# NET.net
KiCad netlist of a schematic drawn in Altium Designer
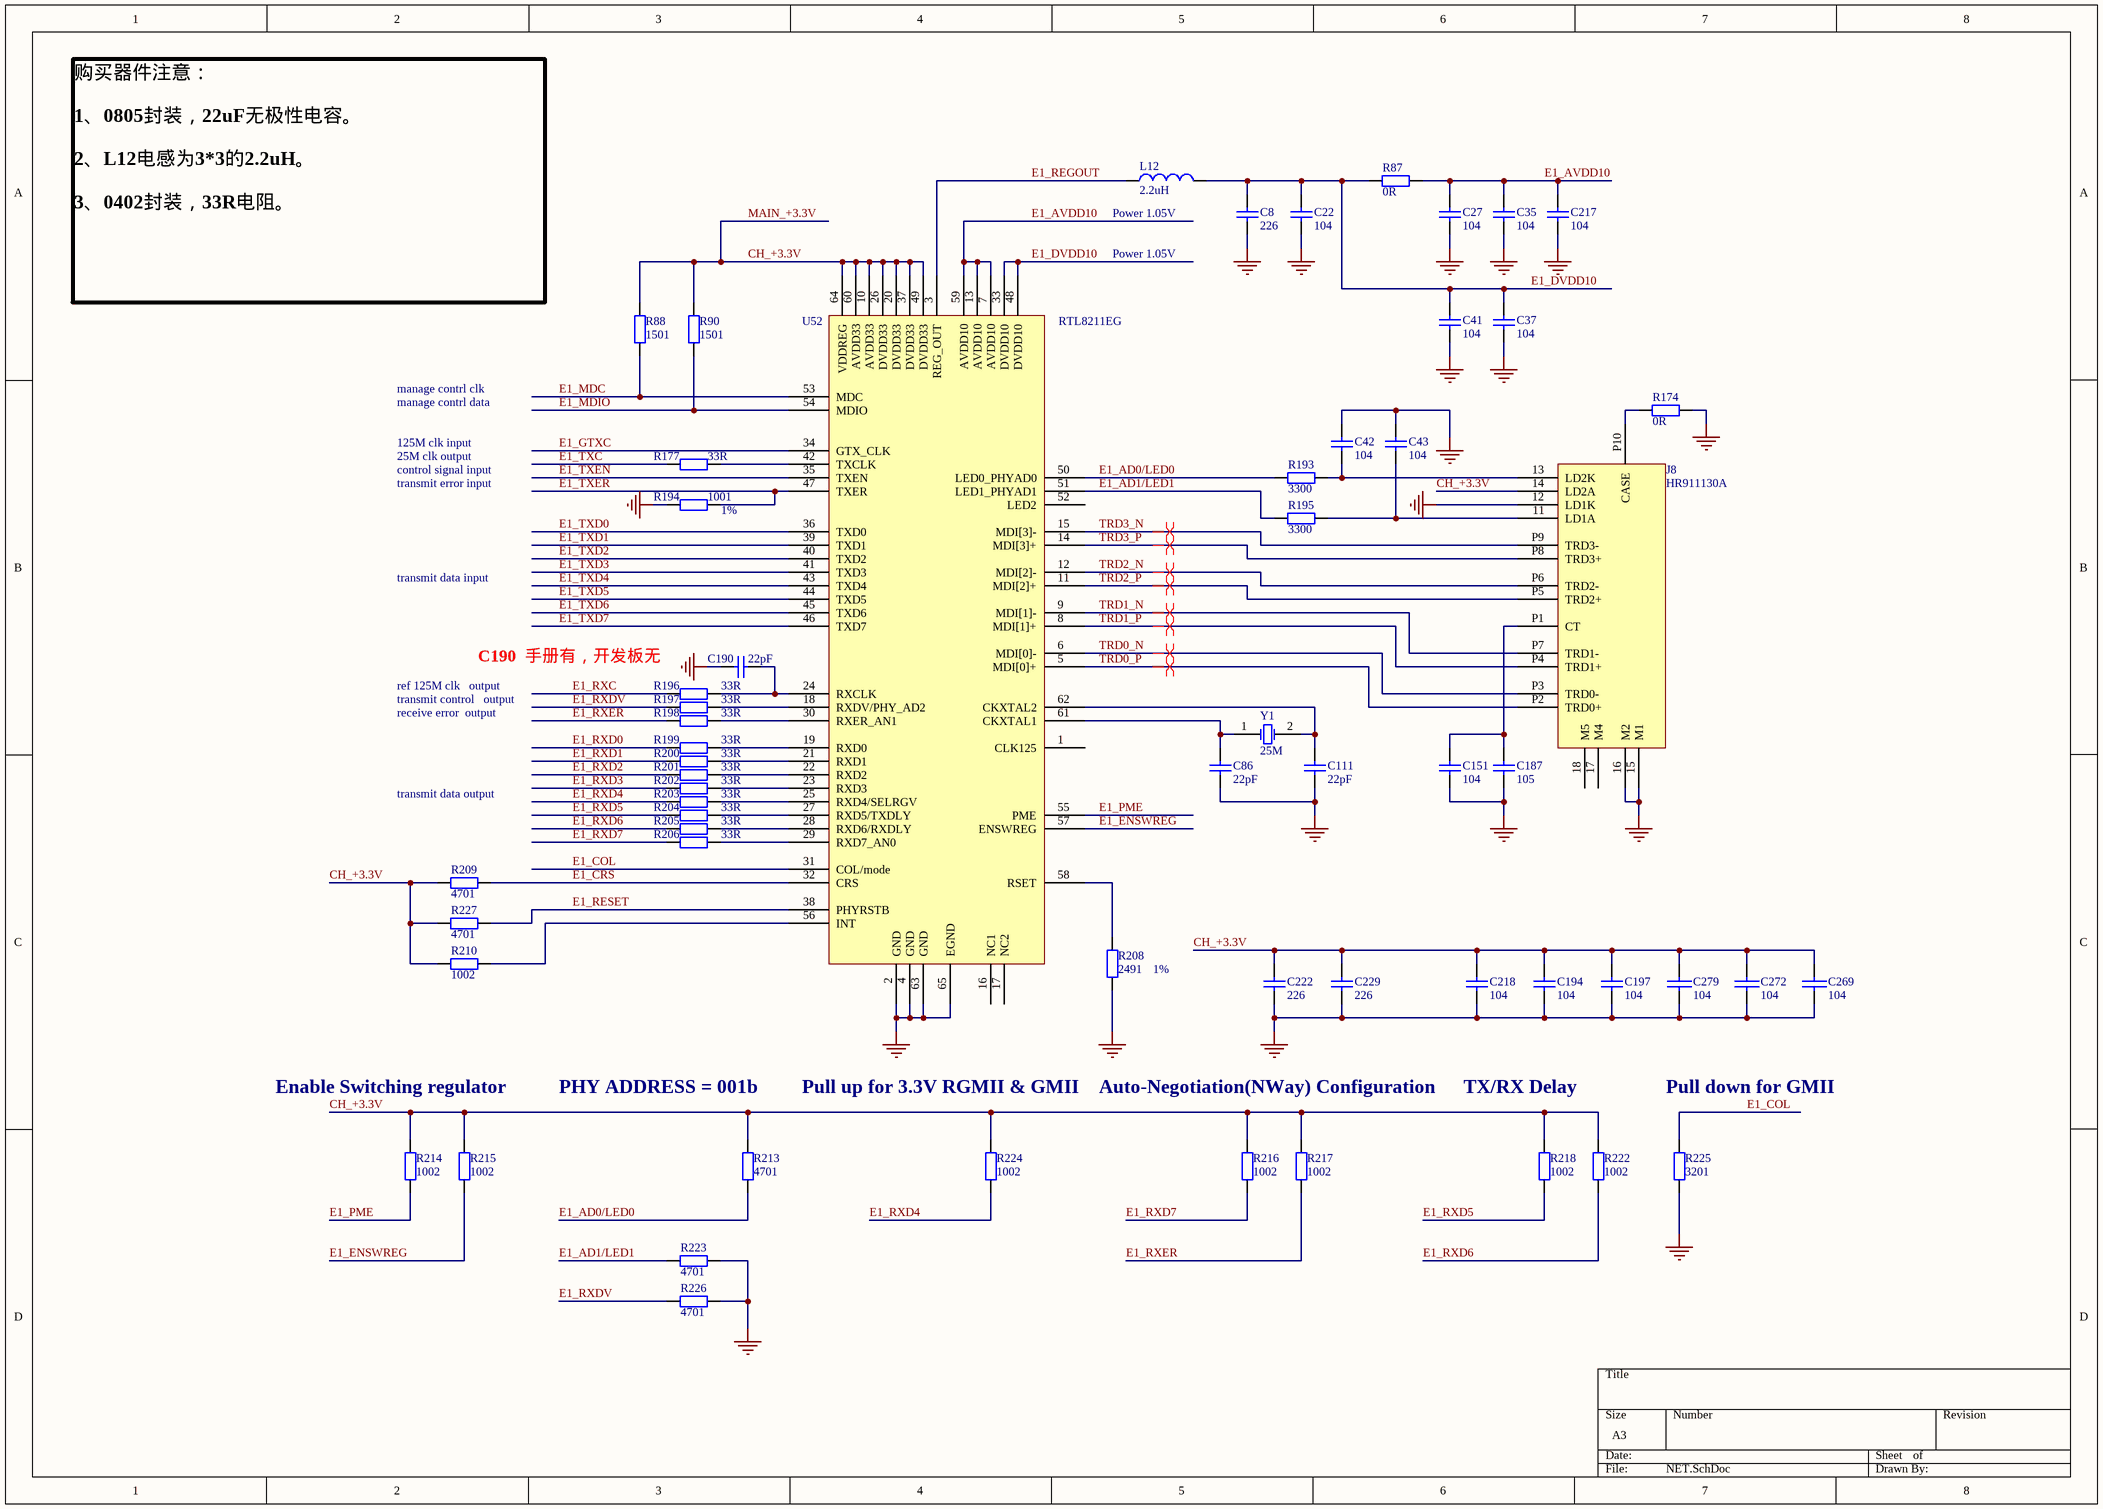
[diagram p0: NET.SchDoc]

(export (version "E")
  (design (tool "Eeschema 10.0.6"))
  (components
    (comp (ref "C8")
      (value "226")
      (footprint "0805")
      (description "Capacitor")
      (fields (field (name "PUBLISHER") "Altium Limited"))
      (libsource (lib "Miscellaneous Devices") (part "Cap"))
    )
    (comp (ref "C22")
      (value "104")
      (footprint "0402C")
      (description "Capacitor")
      (fields (field (name "PUBLISHER") "Altium Limited"))
      (libsource (lib "Miscellaneous Devices") (part "Cap"))
    )
    (comp (ref "C27")
      (value "104")
      (footprint "0402C")
      (description "Capacitor")
      (fields (field (name "PUBLISHER") "Altium Limited"))
      (libsource (lib "Miscellaneous Devices") (part "Cap"))
    )
    (comp (ref "C35")
      (value "104")
      (footprint "0402C")
      (description "Capacitor")
      (fields (field (name "PUBLISHER") "Altium Limited"))
      (libsource (lib "Miscellaneous Devices") (part "Cap"))
    )
    (comp (ref "C37")
      (value "104")
      (footprint "0402C")
      (description "Capacitor")
      (fields (field (name "PUBLISHER") "Altium Limited"))
      (libsource (lib "Miscellaneous Devices") (part "Cap"))
    )
    (comp (ref "C41")
      (value "104")
      (footprint "0402C")
      (description "Capacitor")
      (fields (field (name "PUBLISHER") "Altium Limited"))
      (libsource (lib "Miscellaneous Devices") (part "Cap"))
    )
    (comp (ref "C42")
      (value "104")
      (footprint "0402C")
      (description "Capacitor")
      (fields (field (name "PUBLISHER") "Altium Limited"))
      (libsource (lib "Miscellaneous Devices") (part "Cap"))
    )
    (comp (ref "C43")
      (value "104")
      (footprint "0402C")
      (description "Capacitor")
      (fields (field (name "PUBLISHER") "Altium Limited"))
      (libsource (lib "Miscellaneous Devices") (part "Cap"))
    )
    (comp (ref "C86")
      (value "22pF")
      (footprint "0805")
      (description "Capacitor")
      (fields (field (name "PUBLISHER") "Altium Limited"))
      (libsource (lib "Miscellaneous Devices") (part "Cap"))
    )
    (comp (ref "C111")
      (value "22pF")
      (footprint "0805")
      (description "Capacitor")
      (fields (field (name "PUBLISHER") "Altium Limited"))
      (libsource (lib "Miscellaneous Devices") (part "Cap"))
    )
    (comp (ref "C151")
      (value "104")
      (footprint "0402C")
      (description "Capacitor")
      (fields (field (name "PUBLISHER") "Altium Limited"))
      (libsource (lib "Miscellaneous Devices") (part "Cap"))
    )
    (comp (ref "C187")
      (value "105")
      (footprint "0805")
      (description "Capacitor")
      (fields (field (name "PUBLISHER") "Altium Limited"))
      (libsource (lib "Miscellaneous Devices") (part "Cap"))
    )
    (comp (ref "C190")
      (value "22pF")
      (footprint "0402")
      (description "Capacitor")
      (fields (field (name "PUBLISHER") "Altium Limited"))
      (libsource (lib "Miscellaneous Devices") (part "Cap"))
    )
    (comp (ref "C194")
      (value "104")
      (footprint "0402C")
      (description "Capacitor")
      (fields (field (name "PUBLISHER") "Altium Limited"))
      (libsource (lib "Miscellaneous Devices") (part "Cap"))
    )
    (comp (ref "C197")
      (value "104")
      (footprint "0402C")
      (description "Capacitor")
      (fields (field (name "PUBLISHER") "Altium Limited"))
      (libsource (lib "Miscellaneous Devices") (part "Cap"))
    )
    (comp (ref "C217")
      (value "104")
      (footprint "0402C")
      (description "Capacitor")
      (fields (field (name "PUBLISHER") "Altium Limited"))
      (libsource (lib "Miscellaneous Devices") (part "Cap"))
    )
    (comp (ref "C218")
      (value "104")
      (footprint "0402C")
      (description "Capacitor")
      (fields (field (name "PUBLISHER") "Altium Limited"))
      (libsource (lib "Miscellaneous Devices") (part "Cap"))
    )
    (comp (ref "C222")
      (value "226")
      (footprint "0805")
      (description "Capacitor")
      (fields (field (name "PUBLISHER") "Altium Limited"))
      (libsource (lib "Miscellaneous Devices") (part "Cap"))
    )
    (comp (ref "C229")
      (value "226")
      (footprint "0805")
      (description "Capacitor")
      (fields (field (name "PUBLISHER") "Altium Limited"))
      (libsource (lib "Miscellaneous Devices") (part "Cap"))
    )
    (comp (ref "C269")
      (value "104")
      (footprint "0402C")
      (description "Capacitor")
      (libsource (lib "*") (part "CAP"))
    )
    (comp (ref "C272")
      (value "104")
      (footprint "0402C")
      (description "Capacitor")
      (libsource (lib "*") (part "CAP"))
    )
    (comp (ref "C279")
      (value "104")
      (footprint "0402C")
      (description "Capacitor")
      (libsource (lib "*") (part "CAP"))
    )
    (comp (ref "J8") (value "HR911130A") (footprint "GE_RJ45") (libsource (lib "Schlib1") (part "HR911130A")))
    (comp (ref "L12")
      (value "2.2uH")
      (footprint "L22uH")
      (description "Inductor")
      (fields (field (name "PUBLISHER") "Altium Limited"))
      (libsource (lib "Miscellaneous Devices") (part "Inductor"))
    )
    (comp (ref "R87")
      (value "0R")
      (footprint "R0603")
      (description "Resistor")
      (fields (field (name "PUBLISHER") "Altium Limited"))
      (libsource (lib "") (part "Res2_1"))
    )
    (comp (ref "R88")
      (value "1501")
      (footprint "R0603")
      (description "Resistor")
      (fields (field (name "PUBLISHER") "Altium Limited"))
      (libsource (lib "Miscellaneous Devices") (part "Res2"))
    )
    (comp (ref "R90")
      (value "1501")
      (footprint "R0603")
      (description "Resistor")
      (fields (field (name "PUBLISHER") "Altium Limited"))
      (libsource (lib "Miscellaneous Devices") (part "Res2"))
    )
    (comp (ref "R174")
      (value "0R")
      (footprint "R0603")
      (description "Resistor")
      (fields (field (name "PUBLISHER") "Altium Limited"))
      (libsource (lib "") (part "Res2_3"))
    )
    (comp (ref "R177")
      (value "33R")
      (footprint "0402")
      (description "Resistor")
      (fields (field (name "PUBLISHER") "Altium Limited"))
      (libsource (lib "") (part "Res2_1"))
    )
    (comp (ref "R193")
      (value "3300")
      (footprint "R0603")
      (description "Resistor")
      (fields (field (name "PUBLISHER") "Altium Limited"))
      (libsource (lib "") (part "Res2_1"))
    )
    (comp (ref "R194")
      (value "1001")
      (footprint "R0603")
      (description "Resistor")
      (fields (field (name "PUBLISHER") "Altium Limited"))
      (libsource (lib "") (part "Res2_1"))
    )
    (comp (ref "R195")
      (value "3300")
      (footprint "R0603")
      (description "Resistor")
      (fields (field (name "PUBLISHER") "Altium Limited"))
      (libsource (lib "") (part "Res2_1"))
    )
    (comp (ref "R196")
      (value "33R")
      (footprint "0402")
      (description "Resistor")
      (fields (field (name "PUBLISHER") "Altium Limited"))
      (libsource (lib "") (part "Res2_1"))
    )
    (comp (ref "R197")
      (value "33R")
      (footprint "0402")
      (description "Resistor")
      (fields (field (name "PUBLISHER") "Altium Limited"))
      (libsource (lib "") (part "Res2_1"))
    )
    (comp (ref "R198")
      (value "33R")
      (footprint "0402")
      (description "Resistor")
      (fields (field (name "PUBLISHER") "Altium Limited"))
      (libsource (lib "") (part "Res2_1"))
    )
    (comp (ref "R199")
      (value "33R")
      (footprint "0402")
      (description "Resistor")
      (fields (field (name "PUBLISHER") "Altium Limited"))
      (libsource (lib "") (part "Res2_1"))
    )
    (comp (ref "R200")
      (value "33R")
      (footprint "0402")
      (description "Resistor")
      (fields (field (name "PUBLISHER") "Altium Limited"))
      (libsource (lib "") (part "Res2_1"))
    )
    (comp (ref "R201")
      (value "33R")
      (footprint "0402")
      (description "Resistor")
      (fields (field (name "PUBLISHER") "Altium Limited"))
      (libsource (lib "") (part "Res2_1"))
    )
    (comp (ref "R202")
      (value "33R")
      (footprint "0402")
      (description "Resistor")
      (fields (field (name "PUBLISHER") "Altium Limited"))
      (libsource (lib "") (part "Res2_1"))
    )
    (comp (ref "R203")
      (value "33R")
      (footprint "0402")
      (description "Resistor")
      (fields (field (name "PUBLISHER") "Altium Limited"))
      (libsource (lib "") (part "Res2_1"))
    )
    (comp (ref "R204")
      (value "33R")
      (footprint "0402")
      (description "Resistor")
      (fields (field (name "PUBLISHER") "Altium Limited"))
      (libsource (lib "") (part "Res2_3"))
    )
    (comp (ref "R205")
      (value "33R")
      (footprint "0402")
      (description "Resistor")
      (fields (field (name "PUBLISHER") "Altium Limited"))
      (libsource (lib "") (part "Res2_1"))
    )
    (comp (ref "R206")
      (value "33R")
      (footprint "0402")
      (description "Resistor")
      (fields (field (name "PUBLISHER") "Altium Limited"))
      (libsource (lib "") (part "Res2_1"))
    )
    (comp (ref "R208")
      (value "2491")
      (footprint "R0603")
      (description "Resistor")
      (fields (field (name "PUBLISHER") "Altium Limited"))
      (libsource (lib "") (part "Res2_2"))
    )
    (comp (ref "R209")
      (value "4701")
      (footprint "R0603")
      (description "Resistor")
      (fields (field (name "PUBLISHER") "Altium Limited"))
      (libsource (lib "") (part "Res2_3"))
    )
    (comp (ref "R210")
      (value "1002")
      (footprint "R0603")
      (description "Resistor")
      (fields (field (name "PUBLISHER") "Altium Limited"))
      (libsource (lib "") (part "Res2_1"))
    )
    (comp (ref "R213")
      (value "4701")
      (footprint "R0603")
      (description "Resistor")
      (fields (field (name "PUBLISHER") "Altium Limited"))
      (libsource (lib "Miscellaneous Devices") (part "Res2"))
    )
    (comp (ref "R214")
      (value "1002")
      (footprint "R0603")
      (description "Resistor")
      (fields (field (name "PUBLISHER") "Altium Limited"))
      (libsource (lib "") (part "Res2_2"))
    )
    (comp (ref "R215")
      (value "1002")
      (footprint "R0603")
      (description "Resistor")
      (fields (field (name "PUBLISHER") "Altium Limited"))
      (libsource (lib "") (part "Res2_2"))
    )
    (comp (ref "R216")
      (value "1002")
      (footprint "R0603")
      (description "Resistor")
      (fields (field (name "PUBLISHER") "Altium Limited"))
      (libsource (lib "") (part "Res2_2"))
    )
    (comp (ref "R217")
      (value "1002")
      (footprint "R0603")
      (description "Resistor")
      (fields (field (name "PUBLISHER") "Altium Limited"))
      (libsource (lib "") (part "Res2_2"))
    )
    (comp (ref "R218")
      (value "1002")
      (footprint "R0603")
      (description "Resistor")
      (fields (field (name "PUBLISHER") "Altium Limited"))
      (libsource (lib "") (part "Res2_2"))
    )
    (comp (ref "R222")
      (value "1002")
      (footprint "R0603")
      (description "Resistor")
      (fields (field (name "PUBLISHER") "Altium Limited"))
      (libsource (lib "") (part "Res2_2"))
    )
    (comp (ref "R223")
      (value "4701")
      (footprint "R0603")
      (description "Resistor")
      (fields (field (name "PUBLISHER") "Altium Limited"))
      (libsource (lib "") (part "Res2_3"))
    )
    (comp (ref "R224")
      (value "1002")
      (footprint "R0603")
      (description "Resistor")
      (fields (field (name "PUBLISHER") "Altium Limited"))
      (libsource (lib "") (part "Res2_2"))
    )
    (comp (ref "R225")
      (value "3201")
      (footprint "R0603")
      (description "Resistor")
      (fields (field (name "PUBLISHER") "Altium Limited"))
      (libsource (lib "Miscellaneous Devices") (part "Res2"))
    )
    (comp (ref "R226")
      (value "4701")
      (footprint "R0603")
      (description "Resistor")
      (fields (field (name "PUBLISHER") "Altium Limited"))
      (libsource (lib "") (part "Res2_3"))
    )
    (comp (ref "R227")
      (value "4701")
      (footprint "R0603")
      (description "Resistor")
      (fields (field (name "PUBLISHER") "Altium Limited"))
      (libsource (lib "") (part "Res2_3"))
    )
    (comp (ref "U52")
      (value "RTL8211EG")
      (footprint "QFN65-050-0909")
      (libsource (lib "Schlib1") (part "RTL8211EG"))
    )
    (comp (ref "Y1")
      (value "25M")
      (footprint "XTAL")
      (description "Crystal Oscillator")
      (fields (field (name "PUBLISHER") "Altium Limited"))
      (libsource (lib "Miscellaneous Devices") (part "XTAL"))
    )
  )
  (nets
    (net (code "1") (name "/CH_+3.3V") (class "Default")
      (node (ref "C194") (pin "2") (pinfunction "2_2") (pintype "passive"))
      (node (ref "C197") (pin "2") (pinfunction "2_2") (pintype "passive"))
      (node (ref "C218") (pin "2") (pinfunction "2_2") (pintype "passive"))
      (node (ref "C222") (pin "1") (pinfunction "1_1") (pintype "passive"))
      (node (ref "C229") (pin "1") (pinfunction "1_1") (pintype "passive"))
      (node (ref "C269") (pin "2") (pinfunction "2_2") (pintype "passive"))
      (node (ref "C272") (pin "2") (pinfunction "2_2") (pintype "passive"))
      (node (ref "C279") (pin "2") (pinfunction "2_2") (pintype "passive"))
      (node (ref "J8") (pin "14") (pinfunction "LD2A_14") (pintype "passive"))
      (node (ref "R209") (pin "1") (pinfunction "1_1") (pintype "passive"))
      (node (ref "R210") (pin "2") (pinfunction "2_2") (pintype "passive"))
      (node (ref "R213") (pin "2") (pinfunction "2_2") (pintype "passive"))
      (node (ref "R214") (pin "1") (pinfunction "1_1") (pintype "passive"))
      (node (ref "R215") (pin "1") (pinfunction "1_1") (pintype "passive"))
      (node (ref "R216") (pin "1") (pinfunction "1_1") (pintype "passive"))
      (node (ref "R217") (pin "1") (pinfunction "1_1") (pintype "passive"))
      (node (ref "R218") (pin "1") (pinfunction "1_1") (pintype "passive"))
      (node (ref "R222") (pin "1") (pinfunction "1_1") (pintype "passive"))
      (node (ref "R224") (pin "1") (pinfunction "1_1") (pintype "passive"))
      (node (ref "R227") (pin "1") (pinfunction "1_1") (pintype "passive"))
      (node (ref "R88") (pin "2") (pinfunction "2_2") (pintype "passive"))
      (node (ref "R90") (pin "2") (pinfunction "2_2") (pintype "passive"))
      (node (ref "U52") (pin "10") (pinfunction "AVDD33_10") (pintype "passive"))
      (node (ref "U52") (pin "20") (pinfunction "DVDD33_20") (pintype "passive"))
      (node (ref "U52") (pin "26") (pinfunction "DVDD33_26") (pintype "passive"))
      (node (ref "U52") (pin "37") (pinfunction "DVDD33_37") (pintype "passive"))
      (node (ref "U52") (pin "49") (pinfunction "DVDD33_49") (pintype "passive"))
      (node (ref "U52") (pin "60") (pinfunction "AVDD33_60") (pintype "passive"))
      (node (ref "U52") (pin "64") (pinfunction "VDDREG_64") (pintype "passive"))
    )
    (net (code "2") (name "/E1_AD0{slash}LED0") (class "Default")
      (node (ref "R193") (pin "2") (pinfunction "2_2") (pintype "passive"))
      (node (ref "R213") (pin "1") (pinfunction "1_1") (pintype "passive"))
      (node (ref "U52") (pin "50") (pinfunction "LED0_PHYAD0_50") (pintype "passive"))
    )
    (net (code "3") (name "/E1_AD1{slash}LED1") (class "Default")
      (node (ref "R195") (pin "2") (pinfunction "2_2") (pintype "passive"))
      (node (ref "R223") (pin "1") (pinfunction "1_1") (pintype "passive"))
      (node (ref "U52") (pin "51") (pinfunction "LED1_PHYAD1_51") (pintype "passive"))
    )
    (net (code "4") (name "/E1_AVDD10") (class "Default")
      (node (ref "C217") (pin "2") (pinfunction "2_2") (pintype "passive"))
      (node (ref "C27") (pin "2") (pinfunction "2_2") (pintype "passive"))
      (node (ref "C35") (pin "2") (pinfunction "2_2") (pintype "passive"))
      (node (ref "R87") (pin "1") (pinfunction "1_1") (pintype "passive"))
      (node (ref "U52") (pin "13") (pinfunction "AVDD10_13") (pintype "passive"))
      (node (ref "U52") (pin "59") (pinfunction "AVDD10_59") (pintype "passive"))
      (node (ref "U52") (pin "7") (pinfunction "AVDD10_7") (pintype "passive"))
    )
    (net (code "5") (name "/E1_COL") (class "Default")
      (node (ref "R225") (pin "2") (pinfunction "2_2") (pintype "passive"))
      (node (ref "U52") (pin "31") (pinfunction "COL/mode_31") (pintype "passive"))
    )
    (net (code "6") (name "/E1_CRS") (class "Default")
      (node (ref "R209") (pin "2") (pinfunction "2_2") (pintype "passive"))
      (node (ref "U52") (pin "32") (pinfunction "CRS_32") (pintype "passive"))
    )
    (net (code "7") (name "/E1_DVDD10") (class "Default")
      (node (ref "C22") (pin "2") (pinfunction "2_2") (pintype "passive"))
      (node (ref "C37") (pin "2") (pinfunction "2_2") (pintype "passive"))
      (node (ref "C41") (pin "2") (pinfunction "2_2") (pintype "passive"))
      (node (ref "C8") (pin "1") (pinfunction "1_1") (pintype "passive"))
      (node (ref "L12") (pin "2") (pinfunction "2_2") (pintype "passive"))
      (node (ref "R87") (pin "2") (pinfunction "2_2") (pintype "passive"))
      (node (ref "U52") (pin "33") (pinfunction "DVDD10_33") (pintype "passive"))
      (node (ref "U52") (pin "48") (pinfunction "DVDD10_48") (pintype "passive"))
    )
    (net (code "8") (name "/E1_ENSWREG") (class "Default")
      (node (ref "R215") (pin "2") (pinfunction "2_2") (pintype "passive"))
      (node (ref "U52") (pin "57") (pinfunction "ENSWREG_57") (pintype "passive"))
    )
    (net (code "9") (name "/E1_GTXC") (class "Default")
      (node (ref "U52") (pin "34") (pinfunction "GTX_CLK_34") (pintype "passive"))
    )
    (net (code "10") (name "/E1_MDC") (class "Default")
      (node (ref "R88") (pin "1") (pinfunction "1_1") (pintype "passive"))
      (node (ref "U52") (pin "53") (pinfunction "MDC_53") (pintype "passive"))
    )
    (net (code "11") (name "/E1_MDIO") (class "Default")
      (node (ref "R90") (pin "1") (pinfunction "1_1") (pintype "passive"))
      (node (ref "U52") (pin "54") (pinfunction "MDIO_54") (pintype "passive"))
    )
    (net (code "12") (name "/E1_PME") (class "Default")
      (node (ref "R214") (pin "2") (pinfunction "2_2") (pintype "passive"))
      (node (ref "U52") (pin "55") (pinfunction "PME_55") (pintype "passive"))
    )
    (net (code "13") (name "/E1_REGOUT") (class "Default")
      (node (ref "L12") (pin "1") (pinfunction "1_1") (pintype "passive"))
      (node (ref "U52") (pin "3") (pinfunction "REG_OUT_3") (pintype "passive"))
    )
    (net (code "14") (name "/E1_RESET") (class "Default")
      (node (ref "R227") (pin "2") (pinfunction "2_2") (pintype "passive"))
      (node (ref "U52") (pin "38") (pinfunction "PHYRSTB_38") (pintype "passive"))
    )
    (net (code "15") (name "/E1_RXC") (class "Default")
      (node (ref "R196") (pin "2") (pinfunction "2_2") (pintype "passive"))
    )
    (net (code "16") (name "/E1_RXD0") (class "Default")
      (node (ref "R199") (pin "2") (pinfunction "2_2") (pintype "passive"))
    )
    (net (code "17") (name "/E1_RXD1") (class "Default")
      (node (ref "R200") (pin "2") (pinfunction "2_2") (pintype "passive"))
    )
    (net (code "18") (name "/E1_RXD2") (class "Default")
      (node (ref "R201") (pin "2") (pinfunction "2_2") (pintype "passive"))
    )
    (net (code "19") (name "/E1_RXD3") (class "Default")
      (node (ref "R202") (pin "2") (pinfunction "2_2") (pintype "passive"))
    )
    (net (code "20") (name "/E1_RXD4") (class "Default")
      (node (ref "R203") (pin "2") (pinfunction "2_2") (pintype "passive"))
      (node (ref "R224") (pin "2") (pinfunction "2_2") (pintype "passive"))
    )
    (net (code "21") (name "/E1_RXD5") (class "Default")
      (node (ref "R204") (pin "1") (pinfunction "1_1") (pintype "passive"))
      (node (ref "R218") (pin "2") (pinfunction "2_2") (pintype "passive"))
    )
    (net (code "22") (name "/E1_RXD6") (class "Default")
      (node (ref "R205") (pin "2") (pinfunction "2_2") (pintype "passive"))
      (node (ref "R222") (pin "2") (pinfunction "2_2") (pintype "passive"))
    )
    (net (code "23") (name "/E1_RXD7") (class "Default")
      (node (ref "R206") (pin "2") (pinfunction "2_2") (pintype "passive"))
      (node (ref "R216") (pin "2") (pinfunction "2_2") (pintype "passive"))
    )
    (net (code "24") (name "/E1_RXDV") (class "Default")
      (node (ref "R197") (pin "2") (pinfunction "2_2") (pintype "passive"))
      (node (ref "R226") (pin "1") (pinfunction "1_1") (pintype "passive"))
    )
    (net (code "25") (name "/E1_RXER") (class "Default")
      (node (ref "R198") (pin "2") (pinfunction "2_2") (pintype "passive"))
      (node (ref "R217") (pin "2") (pinfunction "2_2") (pintype "passive"))
    )
    (net (code "26") (name "/E1_TXC") (class "Default")
      (node (ref "R177") (pin "2") (pinfunction "2_2") (pintype "passive"))
    )
    (net (code "27") (name "/E1_TXD0") (class "Default")
      (node (ref "U52") (pin "36") (pinfunction "TXD0_36") (pintype "passive"))
    )
    (net (code "28") (name "/E1_TXD1") (class "Default")
      (node (ref "U52") (pin "39") (pinfunction "TXD1_39") (pintype "passive"))
    )
    (net (code "29") (name "/E1_TXD2") (class "Default")
      (node (ref "U52") (pin "40") (pinfunction "TXD2_40") (pintype "passive"))
    )
    (net (code "30") (name "/E1_TXD3") (class "Default")
      (node (ref "U52") (pin "41") (pinfunction "TXD3_41") (pintype "passive"))
    )
    (net (code "31") (name "/E1_TXD4") (class "Default")
      (node (ref "U52") (pin "43") (pinfunction "TXD4_43") (pintype "passive"))
    )
    (net (code "32") (name "/E1_TXD5") (class "Default")
      (node (ref "U52") (pin "44") (pinfunction "TXD5_44") (pintype "passive"))
    )
    (net (code "33") (name "/E1_TXD6") (class "Default")
      (node (ref "U52") (pin "45") (pinfunction "TXD6_45") (pintype "passive"))
    )
    (net (code "34") (name "/E1_TXD7") (class "Default")
      (node (ref "U52") (pin "46") (pinfunction "TXD7_46") (pintype "passive"))
    )
    (net (code "35") (name "/E1_TXEN") (class "Default")
      (node (ref "U52") (pin "35") (pinfunction "TXEN_35") (pintype "passive"))
    )
    (net (code "36") (name "/E1_TXER") (class "Default")
      (node (ref "R194") (pin "1") (pinfunction "1_1") (pintype "passive"))
      (node (ref "U52") (pin "47") (pinfunction "TXER_47") (pintype "passive"))
    )
    (net (code "37") (name "/TRD0_N") (class "Default")
      (node (ref "J8") (pin "P3") (pinfunction "TRD0-_P3") (pintype "passive"))
      (node (ref "U52") (pin "6") (pinfunction "MDI[0]-_6") (pintype "passive"))
    )
    (net (code "38") (name "/TRD0_P") (class "Default")
      (node (ref "J8") (pin "P2") (pinfunction "TRD0+_P2") (pintype "passive"))
      (node (ref "U52") (pin "5") (pinfunction "MDI[0]+_5") (pintype "passive"))
    )
    (net (code "39") (name "/TRD1_N") (class "Default")
      (node (ref "J8") (pin "P7") (pinfunction "TRD1-_P7") (pintype "passive"))
      (node (ref "U52") (pin "9") (pinfunction "MDI[1]-_9") (pintype "passive"))
    )
    (net (code "40") (name "/TRD1_P") (class "Default")
      (node (ref "J8") (pin "P4") (pinfunction "TRD1+_P4") (pintype "passive"))
      (node (ref "U52") (pin "8") (pinfunction "MDI[1]+_8") (pintype "passive"))
    )
    (net (code "41") (name "/TRD2_N") (class "Default")
      (node (ref "J8") (pin "P6") (pinfunction "TRD2-_P6") (pintype "passive"))
      (node (ref "U52") (pin "12") (pinfunction "MDI[2]-_12") (pintype "passive"))
    )
    (net (code "42") (name "/TRD2_P") (class "Default")
      (node (ref "J8") (pin "P5") (pinfunction "TRD2+_P5") (pintype "passive"))
      (node (ref "U52") (pin "11") (pinfunction "MDI[2]+_11") (pintype "passive"))
    )
    (net (code "43") (name "/TRD3_N") (class "Default")
      (node (ref "J8") (pin "P9") (pinfunction "TRD3-_P9") (pintype "passive"))
      (node (ref "U52") (pin "15") (pinfunction "MDI[3]-_15") (pintype "passive"))
    )
    (net (code "44") (name "/TRD3_P") (class "Default")
      (node (ref "J8") (pin "P8") (pinfunction "TRD3+_P8") (pintype "passive"))
      (node (ref "U52") (pin "14") (pinfunction "MDI[3]+_14") (pintype "passive"))
    )
    (net (code "45") (name "DGND") (class "Default")
      (node (ref "C111") (pin "1") (pinfunction "1_1") (pintype "passive"))
      (node (ref "C151") (pin "1") (pinfunction "1_1") (pintype "passive"))
      (node (ref "C187") (pin "1") (pinfunction "1_1") (pintype "passive"))
      (node (ref "C190") (pin "2") (pinfunction "2_2") (pintype "passive"))
      (node (ref "C194") (pin "1") (pinfunction "1_1") (pintype "passive"))
      (node (ref "C197") (pin "1") (pinfunction "1_1") (pintype "passive"))
      (node (ref "C217") (pin "1") (pinfunction "1_1") (pintype "passive"))
      (node (ref "C218") (pin "1") (pinfunction "1_1") (pintype "passive"))
      (node (ref "C22") (pin "1") (pinfunction "1_1") (pintype "passive"))
      (node (ref "C222") (pin "2") (pinfunction "2_2") (pintype "passive"))
      (node (ref "C229") (pin "2") (pinfunction "2_2") (pintype "passive"))
      (node (ref "C269") (pin "1") (pinfunction "1_1") (pintype "passive"))
      (node (ref "C27") (pin "1") (pinfunction "1_1") (pintype "passive"))
      (node (ref "C272") (pin "1") (pinfunction "1_1") (pintype "passive"))
      (node (ref "C279") (pin "1") (pinfunction "1_1") (pintype "passive"))
      (node (ref "C35") (pin "1") (pinfunction "1_1") (pintype "passive"))
      (node (ref "C37") (pin "1") (pinfunction "1_1") (pintype "passive"))
      (node (ref "C41") (pin "1") (pinfunction "1_1") (pintype "passive"))
      (node (ref "C42") (pin "2") (pinfunction "2_2") (pintype "passive"))
      (node (ref "C43") (pin "2") (pinfunction "2_2") (pintype "passive"))
      (node (ref "C8") (pin "2") (pinfunction "2_2") (pintype "passive"))
      (node (ref "C86") (pin "1") (pinfunction "1_1") (pintype "passive"))
      (node (ref "J8") (pin "12") (pinfunction "LD1K_12") (pintype "passive"))
      (node (ref "J8") (pin "15") (pinfunction "M1_15") (pintype "passive"))
      (node (ref "J8") (pin "16") (pinfunction "M2_16") (pintype "passive"))
      (node (ref "R174") (pin "2") (pinfunction "2_2") (pintype "passive"))
      (node (ref "R194") (pin "2") (pinfunction "2_2") (pintype "passive"))
      (node (ref "R208") (pin "2") (pinfunction "2_2") (pintype "passive"))
      (node (ref "R223") (pin "2") (pinfunction "2_2") (pintype "passive"))
      (node (ref "R225") (pin "1") (pinfunction "1_1") (pintype "passive"))
      (node (ref "R226") (pin "2") (pinfunction "2_2") (pintype "passive"))
      (node (ref "U52") (pin "2") (pinfunction "GND_2") (pintype "passive"))
      (node (ref "U52") (pin "4") (pinfunction "GND_4") (pintype "passive"))
      (node (ref "U52") (pin "63") (pinfunction "GND_63") (pintype "passive"))
      (node (ref "U52") (pin "65") (pinfunction "EGND_65") (pintype "passive"))
    )
    (net (code "46") (name "Net-(J8-CASE)") (class "Default")
      (node (ref "J8") (pin "P10") (pinfunction "CASE_P10") (pintype "passive"))
      (node (ref "R174") (pin "1") (pinfunction "1_1") (pintype "passive"))
    )
    (net (code "47") (name "Net-(J8-CT)") (class "Default")
      (node (ref "C151") (pin "2") (pinfunction "2_2") (pintype "passive"))
      (node (ref "C187") (pin "2") (pinfunction "2_2") (pintype "passive"))
      (node (ref "J8") (pin "P1") (pinfunction "CT_P1") (pintype "passive"))
    )
    (net (code "48") (name "Net-(J8-LD1A)") (class "Default")
      (node (ref "C43") (pin "1") (pinfunction "1_1") (pintype "passive"))
      (node (ref "J8") (pin "11") (pinfunction "LD1A_11") (pintype "passive"))
      (node (ref "R195") (pin "1") (pinfunction "1_1") (pintype "passive"))
    )
    (net (code "49") (name "Net-(J8-LD2K)") (class "Default")
      (node (ref "C42") (pin "1") (pinfunction "1_1") (pintype "passive"))
      (node (ref "J8") (pin "13") (pinfunction "LD2K_13") (pintype "passive"))
      (node (ref "R193") (pin "1") (pinfunction "1_1") (pintype "passive"))
    )
    (net (code "50") (name "Net-(U52-CKXTAL1)") (class "Default")
      (node (ref "C86") (pin "2") (pinfunction "2_2") (pintype "passive"))
      (node (ref "U52") (pin "61") (pinfunction "CKXTAL1_61") (pintype "passive"))
      (node (ref "Y1") (pin "1") (pinfunction "OSC1_1") (pintype "passive"))
    )
    (net (code "51") (name "Net-(U52-CKXTAL2)") (class "Default")
      (node (ref "C111") (pin "2") (pinfunction "2_2") (pintype "passive"))
      (node (ref "U52") (pin "62") (pinfunction "CKXTAL2_62") (pintype "passive"))
      (node (ref "Y1") (pin "2") (pinfunction "OSC2_2") (pintype "passive"))
    )
    (net (code "52") (name "Net-(U52-INT)") (class "Default")
      (node (ref "R210") (pin "1") (pinfunction "1_1") (pintype "passive"))
      (node (ref "U52") (pin "56") (pinfunction "INT_56") (pintype "passive"))
    )
    (net (code "53") (name "Net-(U52-RSET)") (class "Default")
      (node (ref "R208") (pin "1") (pinfunction "1_1") (pintype "passive"))
      (node (ref "U52") (pin "58") (pinfunction "RSET_58") (pintype "passive"))
    )
    (net (code "54") (name "Net-(U52-RXCLK)") (class "Default")
      (node (ref "C190") (pin "1") (pinfunction "1_1") (pintype "passive"))
      (node (ref "R196") (pin "1") (pinfunction "1_1") (pintype "passive"))
      (node (ref "U52") (pin "24") (pinfunction "RXCLK_24") (pintype "passive"))
    )
    (net (code "55") (name "Net-(U52-RXD0)") (class "Default")
      (node (ref "R199") (pin "1") (pinfunction "1_1") (pintype "passive"))
      (node (ref "U52") (pin "19") (pinfunction "RXD0_19") (pintype "passive"))
    )
    (net (code "56") (name "Net-(U52-RXD1)") (class "Default")
      (node (ref "R200") (pin "1") (pinfunction "1_1") (pintype "passive"))
      (node (ref "U52") (pin "21") (pinfunction "RXD1_21") (pintype "passive"))
    )
    (net (code "57") (name "Net-(U52-RXD2)") (class "Default")
      (node (ref "R201") (pin "1") (pinfunction "1_1") (pintype "passive"))
      (node (ref "U52") (pin "22") (pinfunction "RXD2_22") (pintype "passive"))
    )
    (net (code "58") (name "Net-(U52-RXD3)") (class "Default")
      (node (ref "R202") (pin "1") (pinfunction "1_1") (pintype "passive"))
      (node (ref "U52") (pin "23") (pinfunction "RXD3_23") (pintype "passive"))
    )
    (net (code "59") (name "Net-(U52-RXD4{slash}SELRGV)") (class "Default")
      (node (ref "R203") (pin "1") (pinfunction "1_1") (pintype "passive"))
      (node (ref "U52") (pin "25") (pinfunction "RXD4/SELRGV_25") (pintype "passive"))
    )
    (net (code "60") (name "Net-(U52-RXD5{slash}TXDLY)") (class "Default")
      (node (ref "R204") (pin "2") (pinfunction "2_2") (pintype "passive"))
      (node (ref "U52") (pin "27") (pinfunction "RXD5/TXDLY_27") (pintype "passive"))
    )
    (net (code "61") (name "Net-(U52-RXD6{slash}RXDLY)") (class "Default")
      (node (ref "R205") (pin "1") (pinfunction "1_1") (pintype "passive"))
      (node (ref "U52") (pin "28") (pinfunction "RXD6/RXDLY_28") (pintype "passive"))
    )
    (net (code "62") (name "Net-(U52-RXD7_AN0)") (class "Default")
      (node (ref "R206") (pin "1") (pinfunction "1_1") (pintype "passive"))
      (node (ref "U52") (pin "29") (pinfunction "RXD7_AN0_29") (pintype "passive"))
    )
    (net (code "63") (name "Net-(U52-RXDV{slash}PHY_AD2)") (class "Default")
      (node (ref "R197") (pin "1") (pinfunction "1_1") (pintype "passive"))
      (node (ref "U52") (pin "18") (pinfunction "RXDV/PHY_AD2_18") (pintype "passive"))
    )
    (net (code "64") (name "Net-(U52-RXER_AN1)") (class "Default")
      (node (ref "R198") (pin "1") (pinfunction "1_1") (pintype "passive"))
      (node (ref "U52") (pin "30") (pinfunction "RXER_AN1_30") (pintype "passive"))
    )
    (net (code "65") (name "Net-(U52-TXCLK)") (class "Default")
      (node (ref "R177") (pin "1") (pinfunction "1_1") (pintype "passive"))
      (node (ref "U52") (pin "42") (pinfunction "TXCLK_42") (pintype "passive"))
    )
    (net (code "66") (name "unconnected-(J8-M4-Pad17)") (class "Default")
      (node (ref "J8") (pin "17") (pinfunction "M4_17") (pintype "passive"))
    )
    (net (code "67") (name "unconnected-(J8-M5-Pad18)") (class "Default")
      (node (ref "J8") (pin "18") (pinfunction "M5_18") (pintype "passive"))
    )
    (net (code "68") (name "unconnected-(U52-CLK125-Pad1)") (class "Default")
      (node (ref "U52") (pin "1") (pinfunction "CLK125_1") (pintype "passive"))
    )
    (net (code "69") (name "unconnected-(U52-LED2-Pad52)") (class "Default")
      (node (ref "U52") (pin "52") (pinfunction "LED2_52") (pintype "passive"))
    )
    (net (code "70") (name "unconnected-(U52-NC1-Pad16)") (class "Default")
      (node (ref "U52") (pin "16") (pinfunction "NC1_16") (pintype "passive"))
    )
    (net (code "71") (name "unconnected-(U52-NC2-Pad17)") (class "Default")
      (node (ref "U52") (pin "17") (pinfunction "NC2_17") (pintype "passive"))
    )
  )
)
